# connectors.net
KiCad netlist of a schematic drawn in Altium Designer
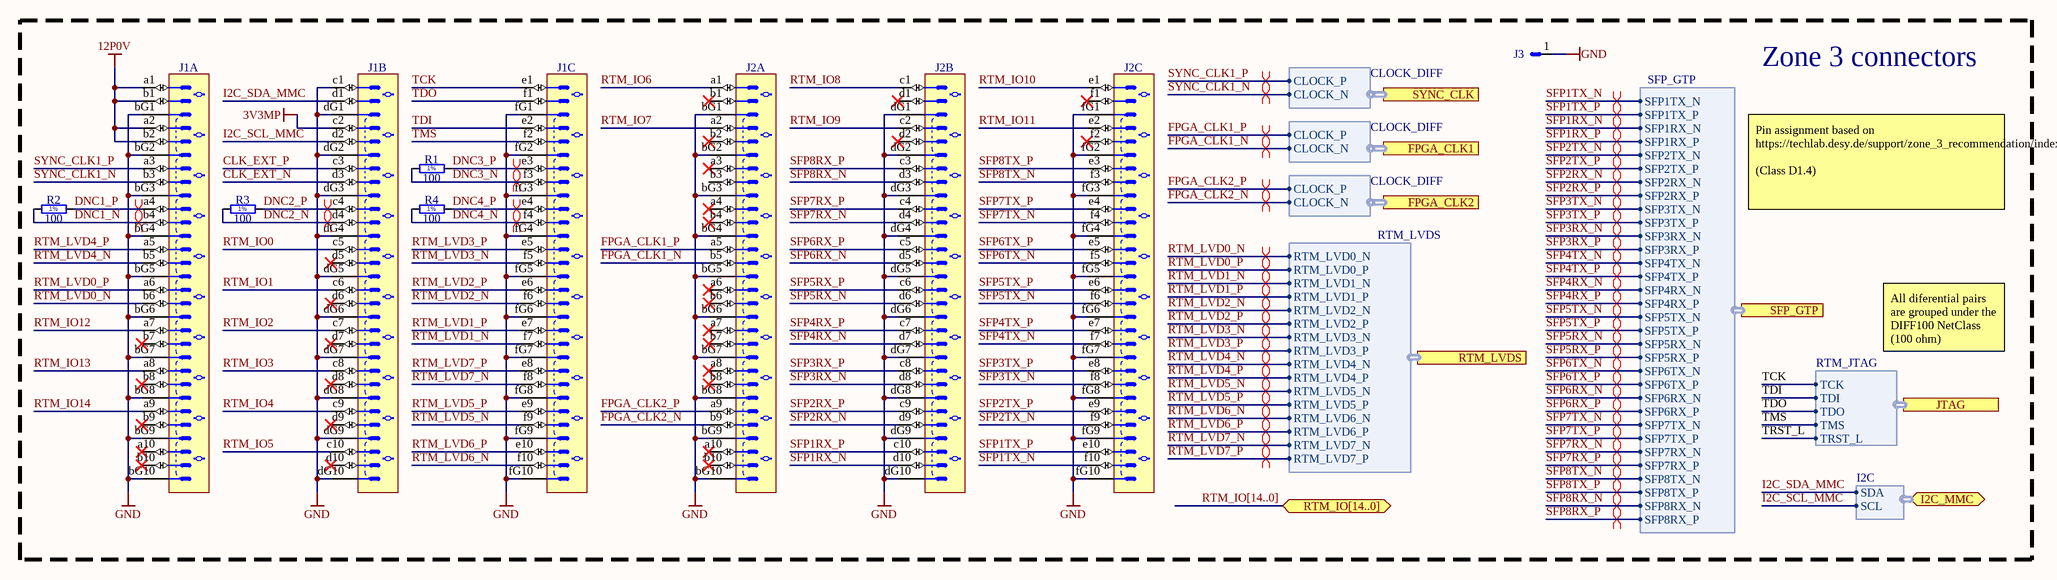
[diagram p0: connectors.SchDoc]

(export (version "E")
  (design (tool "Eeschema 10.0.6"))
  (components
    (comp (ref "J1")
      (value "Advanced TCA")
      (footprint "TYCO_6469183-1")
      (description "Connector 60 ATCA Male 30 Pairs (60 Signals) + 3x10 Ground")
      (fields
        (field (name "PART NUMBER") "TYCO_6469183-1")
        (field (name "MANUFACTURER") "TYCO ELECTRONICS")
        (field (name "AUTHOR") "CERN DEM JLC")
      )
      (libsource (lib "Connectors") (part "Connector ATCA 60+30 Male"))
    )
    (comp (ref "J2")
      (value "Advanced TCA")
      (footprint "TYCO_6469183-1")
      (description "Connector 60 ATCA Male 30 Pairs (60 Signals) + 3x10 Ground")
      (fields
        (field (name "PART NUMBER") "TYCO_6469183-1")
        (field (name "MANUFACTURER") "TYCO ELECTRONICS")
        (field (name "AUTHOR") "CERN DEM JLC")
      )
      (libsource (lib "Connectors") (part "Connector ATCA 60+30 Male"))
    )
    (comp (ref "J3")
      (value "~")
      (footprint "TYCO_1469265-1")
      (description "Single Pin Male")
      (fields
        (field (name "PART NUMBER") "TYCO_1469265-1")
        (field (name "MANUFACTURER") "TYCO ELECTRONICS")
        (field (name "AUTHOR") "CERN DEM JLC")
      )
      (libsource (lib "Connectors") (part "Single Pin Male"))
    )
    (comp (ref "R1")
      (value "100")
      (footprint "RESC1608X55N")
      (description "Resistor - 1%")
      (fields
        (field (name "PART NUMBER") "R0603_100R_1%_0.1W_100PPM")
        (field (name "POWER") "0.1W")
        (field (name "AUTHOR") "CERN DEM JLC")
      )
      (libsource (lib "Resistors") (part "Resistor - 1%"))
    )
    (comp (ref "R2")
      (value "100")
      (footprint "RESC1608X55N")
      (description "Resistor - 1%")
      (fields
        (field (name "PART NUMBER") "R0603_100R_1%_0.1W_100PPM")
        (field (name "POWER") "0.1W")
        (field (name "AUTHOR") "CERN DEM JLC")
      )
      (libsource (lib "Resistors") (part "Resistor - 1%"))
    )
    (comp (ref "R3")
      (value "100")
      (footprint "RESC1608X55N")
      (description "Resistor - 1%")
      (fields
        (field (name "PART NUMBER") "R0603_100R_1%_0.1W_100PPM")
        (field (name "POWER") "0.1W")
        (field (name "AUTHOR") "CERN DEM JLC")
      )
      (libsource (lib "Resistors") (part "Resistor - 1%"))
    )
    (comp (ref "R4")
      (value "100")
      (footprint "RESC1608X55N")
      (description "Resistor - 1%")
      (fields
        (field (name "PART NUMBER") "R0603_100R_1%_0.1W_100PPM")
        (field (name "POWER") "0.1W")
        (field (name "AUTHOR") "CERN DEM JLC")
      )
      (libsource (lib "Resistors") (part "Resistor - 1%"))
    )
  )
  (nets
    (net (code "6") (name "/CLK_EXT_N") (class "Default")
      (node (ref "J1") (pin "d3") (pinfunction "d3_d3") (pintype "bidirectional"))
    )
    (net (code "7") (name "/CLK_EXT_P") (class "Default")
      (node (ref "J1") (pin "c3") (pinfunction "c3_c3") (pintype "bidirectional"))
    )
    (net (code "8") (name "/DNC1_N") (class "Default")
      (node (ref "J1") (pin "b4") (pinfunction "b4_b4") (pintype "bidirectional"))
      (node (ref "R2") (pin "1") (pinfunction "1_1") (pintype "passive"))
    )
    (net (code "9") (name "/DNC1_P") (class "Default")
      (node (ref "J1") (pin "a4") (pinfunction "a4_a4") (pintype "bidirectional"))
      (node (ref "R2") (pin "2") (pinfunction "2_2") (pintype "passive"))
    )
    (net (code "10") (name "/DNC2_N") (class "Default")
      (node (ref "J1") (pin "d4") (pinfunction "d4_d4") (pintype "bidirectional"))
      (node (ref "R3") (pin "1") (pinfunction "1_1") (pintype "passive"))
    )
    (net (code "11") (name "/DNC2_P") (class "Default")
      (node (ref "J1") (pin "c4") (pinfunction "c4_c4") (pintype "bidirectional"))
      (node (ref "R3") (pin "2") (pinfunction "2_2") (pintype "passive"))
    )
    (net (code "12") (name "/DNC3_N") (class "Default")
      (node (ref "J1") (pin "f3") (pinfunction "f3_f3") (pintype "bidirectional"))
      (node (ref "R1") (pin "1") (pinfunction "1_1") (pintype "passive"))
    )
    (net (code "13") (name "/DNC3_P") (class "Default")
      (node (ref "J1") (pin "e3") (pinfunction "e3_e3") (pintype "bidirectional"))
      (node (ref "R1") (pin "2") (pinfunction "2_2") (pintype "passive"))
    )
    (net (code "14") (name "/DNC4_N") (class "Default")
      (node (ref "J1") (pin "f4") (pinfunction "f4_f4") (pintype "bidirectional"))
      (node (ref "R4") (pin "1") (pinfunction "1_1") (pintype "passive"))
    )
    (net (code "15") (name "/DNC4_P") (class "Default")
      (node (ref "J1") (pin "e4") (pinfunction "e4_e4") (pintype "bidirectional"))
      (node (ref "R4") (pin "2") (pinfunction "2_2") (pintype "passive"))
    )
    (net (code "16") (name "/FPGA_CLK1_N") (class "Default")
      (node (ref "J2") (pin "b5") (pinfunction "b5_b5") (pintype "bidirectional"))
    )
    (net (code "17") (name "/FPGA_CLK1_P") (class "Default")
      (node (ref "J2") (pin "a5") (pinfunction "a5_a5") (pintype "bidirectional"))
    )
    (net (code "18") (name "/FPGA_CLK2_N") (class "Default")
      (node (ref "J2") (pin "b9") (pinfunction "b9_b9") (pintype "bidirectional"))
    )
    (net (code "19") (name "/FPGA_CLK2_P") (class "Default")
      (node (ref "J2") (pin "a9") (pinfunction "a9_a9") (pintype "bidirectional"))
    )
    (net (code "20") (name "/I2C_SCL_MMC") (class "Default")
      (node (ref "J1") (pin "d2") (pinfunction "d2_d2") (pintype "bidirectional"))
    )
    (net (code "21") (name "/I2C_SDA_MMC") (class "Default")
      (node (ref "J1") (pin "d1") (pinfunction "d1_d1") (pintype "bidirectional"))
    )
    (net (code "22") (name "/RTM_IO0") (class "Default")
      (node (ref "J1") (pin "c5") (pinfunction "c5_c5") (pintype "bidirectional"))
    )
    (net (code "23") (name "/RTM_IO1") (class "Default")
      (node (ref "J1") (pin "c6") (pinfunction "c6_c6") (pintype "bidirectional"))
    )
    (net (code "24") (name "/RTM_IO2") (class "Default")
      (node (ref "J1") (pin "c7") (pinfunction "c7_c7") (pintype "bidirectional"))
    )
    (net (code "25") (name "/RTM_IO3") (class "Default")
      (node (ref "J1") (pin "c8") (pinfunction "c8_c8") (pintype "bidirectional"))
    )
    (net (code "26") (name "/RTM_IO4") (class "Default")
      (node (ref "J1") (pin "c9") (pinfunction "c9_c9") (pintype "bidirectional"))
    )
    (net (code "27") (name "/RTM_IO5") (class "Default")
      (node (ref "J1") (pin "c10") (pinfunction "c10_c10") (pintype "bidirectional"))
    )
    (net (code "28") (name "/RTM_IO6") (class "Default")
      (node (ref "J2") (pin "a1") (pinfunction "a1_a1") (pintype "bidirectional"))
    )
    (net (code "29") (name "/RTM_IO7") (class "Default")
      (node (ref "J2") (pin "a2") (pinfunction "a2_a2") (pintype "bidirectional"))
    )
    (net (code "30") (name "/RTM_IO8") (class "Default")
      (node (ref "J2") (pin "c1") (pinfunction "c1_c1") (pintype "bidirectional"))
    )
    (net (code "31") (name "/RTM_IO9") (class "Default")
      (node (ref "J2") (pin "c2") (pinfunction "c2_c2") (pintype "bidirectional"))
    )
    (net (code "32") (name "/RTM_IO10") (class "Default")
      (node (ref "J2") (pin "e1") (pinfunction "e1_e1") (pintype "bidirectional"))
    )
    (net (code "33") (name "/RTM_IO11") (class "Default")
      (node (ref "J2") (pin "e2") (pinfunction "e2_e2") (pintype "bidirectional"))
    )
    (net (code "34") (name "/RTM_IO12") (class "Default")
      (node (ref "J1") (pin "a7") (pinfunction "a7_a7") (pintype "bidirectional"))
    )
    (net (code "35") (name "/RTM_IO13") (class "Default")
      (node (ref "J1") (pin "a8") (pinfunction "a8_a8") (pintype "bidirectional"))
    )
    (net (code "36") (name "/RTM_IO14") (class "Default")
      (node (ref "J1") (pin "a9") (pinfunction "a9_a9") (pintype "bidirectional"))
    )
    (net (code "38") (name "/RTM_LVD0_N") (class "Default")
      (node (ref "J1") (pin "b6") (pinfunction "b6_b6") (pintype "bidirectional"))
    )
    (net (code "39") (name "/RTM_LVD0_P") (class "Default")
      (node (ref "J1") (pin "a6") (pinfunction "a6_a6") (pintype "bidirectional"))
    )
    (net (code "40") (name "/RTM_LVD1_N") (class "Default")
      (node (ref "J1") (pin "f7") (pinfunction "f7_f7") (pintype "bidirectional"))
    )
    (net (code "41") (name "/RTM_LVD1_P") (class "Default")
      (node (ref "J1") (pin "e7") (pinfunction "e7_e7") (pintype "bidirectional"))
    )
    (net (code "42") (name "/RTM_LVD2_N") (class "Default")
      (node (ref "J1") (pin "f6") (pinfunction "f6_f6") (pintype "bidirectional"))
    )
    (net (code "43") (name "/RTM_LVD2_P") (class "Default")
      (node (ref "J1") (pin "e6") (pinfunction "e6_e6") (pintype "bidirectional"))
    )
    (net (code "44") (name "/RTM_LVD3_N") (class "Default")
      (node (ref "J1") (pin "f5") (pinfunction "f5_f5") (pintype "bidirectional"))
    )
    (net (code "45") (name "/RTM_LVD3_P") (class "Default")
      (node (ref "J1") (pin "e5") (pinfunction "e5_e5") (pintype "bidirectional"))
    )
    (net (code "46") (name "/RTM_LVD4_N") (class "Default")
      (node (ref "J1") (pin "b5") (pinfunction "b5_b5") (pintype "bidirectional"))
    )
    (net (code "47") (name "/RTM_LVD4_P") (class "Default")
      (node (ref "J1") (pin "a5") (pinfunction "a5_a5") (pintype "bidirectional"))
    )
    (net (code "48") (name "/RTM_LVD5_N") (class "Default")
      (node (ref "J1") (pin "f9") (pinfunction "f9_f9") (pintype "bidirectional"))
    )
    (net (code "49") (name "/RTM_LVD5_P") (class "Default")
      (node (ref "J1") (pin "e9") (pinfunction "e9_e9") (pintype "bidirectional"))
    )
    (net (code "50") (name "/RTM_LVD6_N") (class "Default")
      (node (ref "J1") (pin "f10") (pinfunction "f10_f10") (pintype "bidirectional"))
    )
    (net (code "51") (name "/RTM_LVD6_P") (class "Default")
      (node (ref "J1") (pin "e10") (pinfunction "e10_e10") (pintype "bidirectional"))
    )
    (net (code "52") (name "/RTM_LVD7_N") (class "Default")
      (node (ref "J1") (pin "f8") (pinfunction "f8_f8") (pintype "bidirectional"))
    )
    (net (code "53") (name "/RTM_LVD7_P") (class "Default")
      (node (ref "J1") (pin "e8") (pinfunction "e8_e8") (pintype "bidirectional"))
    )
    (net (code "54") (name "/SFP1RX_N") (class "Default")
      (node (ref "J2") (pin "d10") (pinfunction "d10_d10") (pintype "bidirectional"))
    )
    (net (code "55") (name "/SFP1RX_P") (class "Default")
      (node (ref "J2") (pin "c10") (pinfunction "c10_c10") (pintype "bidirectional"))
    )
    (net (code "56") (name "/SFP1TX_N") (class "Default")
      (node (ref "J2") (pin "f10") (pinfunction "f10_f10") (pintype "bidirectional"))
    )
    (net (code "57") (name "/SFP1TX_P") (class "Default")
      (node (ref "J2") (pin "e10") (pinfunction "e10_e10") (pintype "bidirectional"))
    )
    (net (code "58") (name "/SFP2RX_N") (class "Default")
      (node (ref "J2") (pin "d9") (pinfunction "d9_d9") (pintype "bidirectional"))
    )
    (net (code "59") (name "/SFP2RX_P") (class "Default")
      (node (ref "J2") (pin "c9") (pinfunction "c9_c9") (pintype "bidirectional"))
    )
    (net (code "60") (name "/SFP2TX_N") (class "Default")
      (node (ref "J2") (pin "f9") (pinfunction "f9_f9") (pintype "bidirectional"))
    )
    (net (code "61") (name "/SFP2TX_P") (class "Default")
      (node (ref "J2") (pin "e9") (pinfunction "e9_e9") (pintype "bidirectional"))
    )
    (net (code "62") (name "/SFP3RX_N") (class "Default")
      (node (ref "J2") (pin "d8") (pinfunction "d8_d8") (pintype "bidirectional"))
    )
    (net (code "63") (name "/SFP3RX_P") (class "Default")
      (node (ref "J2") (pin "c8") (pinfunction "c8_c8") (pintype "bidirectional"))
    )
    (net (code "64") (name "/SFP3TX_N") (class "Default")
      (node (ref "J2") (pin "f8") (pinfunction "f8_f8") (pintype "bidirectional"))
    )
    (net (code "65") (name "/SFP3TX_P") (class "Default")
      (node (ref "J2") (pin "e8") (pinfunction "e8_e8") (pintype "bidirectional"))
    )
    (net (code "66") (name "/SFP4RX_N") (class "Default")
      (node (ref "J2") (pin "d7") (pinfunction "d7_d7") (pintype "bidirectional"))
    )
    (net (code "67") (name "/SFP4RX_P") (class "Default")
      (node (ref "J2") (pin "c7") (pinfunction "c7_c7") (pintype "bidirectional"))
    )
    (net (code "68") (name "/SFP4TX_N") (class "Default")
      (node (ref "J2") (pin "f7") (pinfunction "f7_f7") (pintype "bidirectional"))
    )
    (net (code "69") (name "/SFP4TX_P") (class "Default")
      (node (ref "J2") (pin "e7") (pinfunction "e7_e7") (pintype "bidirectional"))
    )
    (net (code "70") (name "/SFP5RX_N") (class "Default")
      (node (ref "J2") (pin "d6") (pinfunction "d6_d6") (pintype "bidirectional"))
    )
    (net (code "71") (name "/SFP5RX_P") (class "Default")
      (node (ref "J2") (pin "c6") (pinfunction "c6_c6") (pintype "bidirectional"))
    )
    (net (code "72") (name "/SFP5TX_N") (class "Default")
      (node (ref "J2") (pin "f6") (pinfunction "f6_f6") (pintype "bidirectional"))
    )
    (net (code "73") (name "/SFP5TX_P") (class "Default")
      (node (ref "J2") (pin "e6") (pinfunction "e6_e6") (pintype "bidirectional"))
    )
    (net (code "74") (name "/SFP6RX_N") (class "Default")
      (node (ref "J2") (pin "d5") (pinfunction "d5_d5") (pintype "bidirectional"))
    )
    (net (code "75") (name "/SFP6RX_P") (class "Default")
      (node (ref "J2") (pin "c5") (pinfunction "c5_c5") (pintype "bidirectional"))
    )
    (net (code "76") (name "/SFP6TX_N") (class "Default")
      (node (ref "J2") (pin "f5") (pinfunction "f5_f5") (pintype "bidirectional"))
    )
    (net (code "77") (name "/SFP6TX_P") (class "Default")
      (node (ref "J2") (pin "e5") (pinfunction "e5_e5") (pintype "bidirectional"))
    )
    (net (code "78") (name "/SFP7RX_N") (class "Default")
      (node (ref "J2") (pin "d4") (pinfunction "d4_d4") (pintype "bidirectional"))
    )
    (net (code "79") (name "/SFP7RX_P") (class "Default")
      (node (ref "J2") (pin "c4") (pinfunction "c4_c4") (pintype "bidirectional"))
    )
    (net (code "80") (name "/SFP7TX_N") (class "Default")
      (node (ref "J2") (pin "f4") (pinfunction "f4_f4") (pintype "bidirectional"))
    )
    (net (code "81") (name "/SFP7TX_P") (class "Default")
      (node (ref "J2") (pin "e4") (pinfunction "e4_e4") (pintype "bidirectional"))
    )
    (net (code "82") (name "/SFP8RX_N") (class "Default")
      (node (ref "J2") (pin "d3") (pinfunction "d3_d3") (pintype "bidirectional"))
    )
    (net (code "83") (name "/SFP8RX_P") (class "Default")
      (node (ref "J2") (pin "c3") (pinfunction "c3_c3") (pintype "bidirectional"))
    )
    (net (code "84") (name "/SFP8TX_N") (class "Default")
      (node (ref "J2") (pin "f3") (pinfunction "f3_f3") (pintype "bidirectional"))
    )
    (net (code "85") (name "/SFP8TX_P") (class "Default")
      (node (ref "J2") (pin "e3") (pinfunction "e3_e3") (pintype "bidirectional"))
    )
    (net (code "86") (name "/SYNC_CLK1_N") (class "Default")
      (node (ref "J1") (pin "b3") (pinfunction "b3_b3") (pintype "bidirectional"))
    )
    (net (code "87") (name "/SYNC_CLK1_P") (class "Default")
      (node (ref "J1") (pin "a3") (pinfunction "a3_a3") (pintype "bidirectional"))
    )
    (net (code "88") (name "/TCK") (class "Default")
      (node (ref "J1") (pin "e1") (pinfunction "e1_e1") (pintype "bidirectional"))
    )
    (net (code "89") (name "/TDI") (class "Default")
      (node (ref "J1") (pin "e2") (pinfunction "e2_e2") (pintype "bidirectional"))
    )
    (net (code "90") (name "/TDO") (class "Default")
      (node (ref "J1") (pin "f1") (pinfunction "f1_f1") (pintype "bidirectional"))
    )
    (net (code "91") (name "/TMS") (class "Default")
      (node (ref "J1") (pin "f2") (pinfunction "f2_f2") (pintype "bidirectional"))
    )
    (net (code "98") (name "3V3MP") (class "Default")
      (node (ref "J1") (pin "c2") (pinfunction "c2_c2") (pintype "bidirectional"))
    )
    (net (code "99") (name "12P0V") (class "Default")
      (node (ref "J1") (pin "a1") (pinfunction "a1_a1") (pintype "bidirectional"))
      (node (ref "J1") (pin "a2") (pinfunction "a2_a2") (pintype "bidirectional"))
      (node (ref "J1") (pin "b1") (pinfunction "b1_b1") (pintype "bidirectional"))
      (node (ref "J1") (pin "b2") (pinfunction "b2_b2") (pintype "bidirectional"))
    )
    (net (code "100") (name "GND") (class "Default")
      (node (ref "J1") (pin "bG1") (pinfunction "bG1_bG1") (pintype "power_in"))
      (node (ref "J1") (pin "bG10") (pinfunction "bG10_bG10") (pintype "power_in"))
      (node (ref "J1") (pin "bG2") (pinfunction "bG2_bG2") (pintype "power_in"))
      (node (ref "J1") (pin "bG3") (pinfunction "bG3_bG3") (pintype "power_in"))
      (node (ref "J1") (pin "bG4") (pinfunction "bG4_bG4") (pintype "power_in"))
      (node (ref "J1") (pin "bG5") (pinfunction "bG5_bG5") (pintype "power_in"))
      (node (ref "J1") (pin "bG6") (pinfunction "bG6_bG6") (pintype "power_in"))
      (node (ref "J1") (pin "bG7") (pinfunction "bG7_bG7") (pintype "power_in"))
      (node (ref "J1") (pin "bG8") (pinfunction "bG8_bG8") (pintype "power_in"))
      (node (ref "J1") (pin "bG9") (pinfunction "bG9_bG9") (pintype "power_in"))
      (node (ref "J1") (pin "c1") (pinfunction "c1_c1") (pintype "bidirectional"))
      (node (ref "J1") (pin "dG1") (pinfunction "dG1_dG1") (pintype "power_in"))
      (node (ref "J1") (pin "dG10") (pinfunction "dG10_dG10") (pintype "power_in"))
      (node (ref "J1") (pin "dG2") (pinfunction "dG2_dG2") (pintype "power_in"))
      (node (ref "J1") (pin "dG3") (pinfunction "dG3_dG3") (pintype "power_in"))
      (node (ref "J1") (pin "dG4") (pinfunction "dG4_dG4") (pintype "power_in"))
      (node (ref "J1") (pin "dG5") (pinfunction "dG5_dG5") (pintype "power_in"))
      (node (ref "J1") (pin "dG6") (pinfunction "dG6_dG6") (pintype "power_in"))
      (node (ref "J1") (pin "dG7") (pinfunction "dG7_dG7") (pintype "power_in"))
      (node (ref "J1") (pin "dG8") (pinfunction "dG8_dG8") (pintype "power_in"))
      (node (ref "J1") (pin "dG9") (pinfunction "dG9_dG9") (pintype "power_in"))
      (node (ref "J1") (pin "fG1") (pinfunction "fG1_fG1") (pintype "power_in"))
      (node (ref "J1") (pin "fG10") (pinfunction "fG10_fG10") (pintype "power_in"))
      (node (ref "J1") (pin "fG2") (pinfunction "fG2_fG2") (pintype "power_in"))
      (node (ref "J1") (pin "fG3") (pinfunction "fG3_fG3") (pintype "power_in"))
      (node (ref "J1") (pin "fG4") (pinfunction "fG4_fG4") (pintype "power_in"))
      (node (ref "J1") (pin "fG5") (pinfunction "fG5_fG5") (pintype "power_in"))
      (node (ref "J1") (pin "fG6") (pinfunction "fG6_fG6") (pintype "power_in"))
      (node (ref "J1") (pin "fG7") (pinfunction "fG7_fG7") (pintype "power_in"))
      (node (ref "J1") (pin "fG8") (pinfunction "fG8_fG8") (pintype "power_in"))
      (node (ref "J1") (pin "fG9") (pinfunction "fG9_fG9") (pintype "power_in"))
      (node (ref "J2") (pin "bG1") (pinfunction "bG1_bG1") (pintype "power_in"))
      (node (ref "J2") (pin "bG10") (pinfunction "bG10_bG10") (pintype "power_in"))
      (node (ref "J2") (pin "bG2") (pinfunction "bG2_bG2") (pintype "power_in"))
      (node (ref "J2") (pin "bG3") (pinfunction "bG3_bG3") (pintype "power_in"))
      (node (ref "J2") (pin "bG4") (pinfunction "bG4_bG4") (pintype "power_in"))
      (node (ref "J2") (pin "bG5") (pinfunction "bG5_bG5") (pintype "power_in"))
      (node (ref "J2") (pin "bG6") (pinfunction "bG6_bG6") (pintype "power_in"))
      (node (ref "J2") (pin "bG7") (pinfunction "bG7_bG7") (pintype "power_in"))
      (node (ref "J2") (pin "bG8") (pinfunction "bG8_bG8") (pintype "power_in"))
      (node (ref "J2") (pin "bG9") (pinfunction "bG9_bG9") (pintype "power_in"))
      (node (ref "J2") (pin "dG1") (pinfunction "dG1_dG1") (pintype "power_in"))
      (node (ref "J2") (pin "dG10") (pinfunction "dG10_dG10") (pintype "power_in"))
      (node (ref "J2") (pin "dG2") (pinfunction "dG2_dG2") (pintype "power_in"))
      (node (ref "J2") (pin "dG3") (pinfunction "dG3_dG3") (pintype "power_in"))
      (node (ref "J2") (pin "dG4") (pinfunction "dG4_dG4") (pintype "power_in"))
      (node (ref "J2") (pin "dG5") (pinfunction "dG5_dG5") (pintype "power_in"))
      (node (ref "J2") (pin "dG6") (pinfunction "dG6_dG6") (pintype "power_in"))
      (node (ref "J2") (pin "dG7") (pinfunction "dG7_dG7") (pintype "power_in"))
      (node (ref "J2") (pin "dG8") (pinfunction "dG8_dG8") (pintype "power_in"))
      (node (ref "J2") (pin "dG9") (pinfunction "dG9_dG9") (pintype "power_in"))
      (node (ref "J2") (pin "fG1") (pinfunction "fG1_fG1") (pintype "power_in"))
      (node (ref "J2") (pin "fG10") (pinfunction "fG10_fG10") (pintype "power_in"))
      (node (ref "J2") (pin "fG2") (pinfunction "fG2_fG2") (pintype "power_in"))
      (node (ref "J2") (pin "fG3") (pinfunction "fG3_fG3") (pintype "power_in"))
      (node (ref "J2") (pin "fG4") (pinfunction "fG4_fG4") (pintype "power_in"))
      (node (ref "J2") (pin "fG5") (pinfunction "fG5_fG5") (pintype "power_in"))
      (node (ref "J2") (pin "fG6") (pinfunction "fG6_fG6") (pintype "power_in"))
      (node (ref "J2") (pin "fG7") (pinfunction "fG7_fG7") (pintype "power_in"))
      (node (ref "J2") (pin "fG8") (pinfunction "fG8_fG8") (pintype "power_in"))
      (node (ref "J2") (pin "fG9") (pinfunction "fG9_fG9") (pintype "power_in"))
      (node (ref "J3") (pin "1") (pinfunction "1_1") (pintype "bidirectional"))
    )
    (net (code "101") (name "unconnected-(J1-Pada10)") (class "Default")
      (node (ref "J1") (pin "a10") (pinfunction "a10_a10") (pintype "bidirectional+no_connect"))
    )
    (net (code "102") (name "unconnected-(J1-Padb7)") (class "Default")
      (node (ref "J1") (pin "b7") (pinfunction "b7_b7") (pintype "bidirectional+no_connect"))
    )
    (net (code "103") (name "unconnected-(J1-Padb8)") (class "Default")
      (node (ref "J1") (pin "b8") (pinfunction "b8_b8") (pintype "bidirectional+no_connect"))
    )
    (net (code "104") (name "unconnected-(J1-Padb9)") (class "Default")
      (node (ref "J1") (pin "b9") (pinfunction "b9_b9") (pintype "bidirectional+no_connect"))
    )
    (net (code "105") (name "unconnected-(J1-Padb10)") (class "Default")
      (node (ref "J1") (pin "b10") (pinfunction "b10_b10") (pintype "bidirectional+no_connect"))
    )
    (net (code "106") (name "unconnected-(J1-Padd5)") (class "Default")
      (node (ref "J1") (pin "d5") (pinfunction "d5_d5") (pintype "bidirectional+no_connect"))
    )
    (net (code "107") (name "unconnected-(J1-Padd6)") (class "Default")
      (node (ref "J1") (pin "d6") (pinfunction "d6_d6") (pintype "bidirectional+no_connect"))
    )
    (net (code "108") (name "unconnected-(J1-Padd7)") (class "Default")
      (node (ref "J1") (pin "d7") (pinfunction "d7_d7") (pintype "bidirectional+no_connect"))
    )
    (net (code "109") (name "unconnected-(J1-Padd8)") (class "Default")
      (node (ref "J1") (pin "d8") (pinfunction "d8_d8") (pintype "bidirectional+no_connect"))
    )
    (net (code "110") (name "unconnected-(J1-Padd9)") (class "Default")
      (node (ref "J1") (pin "d9") (pinfunction "d9_d9") (pintype "bidirectional+no_connect"))
    )
    (net (code "111") (name "unconnected-(J1-Padd10)") (class "Default")
      (node (ref "J1") (pin "d10") (pinfunction "d10_d10") (pintype "bidirectional+no_connect"))
    )
    (net (code "112") (name "unconnected-(J2-Pada3)") (class "Default")
      (node (ref "J2") (pin "a3") (pinfunction "a3_a3") (pintype "bidirectional+no_connect"))
    )
    (net (code "113") (name "unconnected-(J2-Pada4)") (class "Default")
      (node (ref "J2") (pin "a4") (pinfunction "a4_a4") (pintype "bidirectional+no_connect"))
    )
    (net (code "114") (name "unconnected-(J2-Pada6)") (class "Default")
      (node (ref "J2") (pin "a6") (pinfunction "a6_a6") (pintype "bidirectional+no_connect"))
    )
    (net (code "115") (name "unconnected-(J2-Pada7)") (class "Default")
      (node (ref "J2") (pin "a7") (pinfunction "a7_a7") (pintype "bidirectional+no_connect"))
    )
    (net (code "116") (name "unconnected-(J2-Pada8)") (class "Default")
      (node (ref "J2") (pin "a8") (pinfunction "a8_a8") (pintype "bidirectional+no_connect"))
    )
    (net (code "117") (name "unconnected-(J2-Pada10)") (class "Default")
      (node (ref "J2") (pin "a10") (pinfunction "a10_a10") (pintype "bidirectional+no_connect"))
    )
    (net (code "118") (name "unconnected-(J2-Padb1)") (class "Default")
      (node (ref "J2") (pin "b1") (pinfunction "b1_b1") (pintype "bidirectional+no_connect"))
    )
    (net (code "119") (name "unconnected-(J2-Padb2)") (class "Default")
      (node (ref "J2") (pin "b2") (pinfunction "b2_b2") (pintype "bidirectional+no_connect"))
    )
    (net (code "120") (name "unconnected-(J2-Padb3)") (class "Default")
      (node (ref "J2") (pin "b3") (pinfunction "b3_b3") (pintype "bidirectional"))
    )
    (net (code "121") (name "unconnected-(J2-Padb4)") (class "Default")
      (node (ref "J2") (pin "b4") (pinfunction "b4_b4") (pintype "bidirectional+no_connect"))
    )
    (net (code "122") (name "unconnected-(J2-Padb6)") (class "Default")
      (node (ref "J2") (pin "b6") (pinfunction "b6_b6") (pintype "bidirectional+no_connect"))
    )
    (net (code "123") (name "unconnected-(J2-Padb7)") (class "Default")
      (node (ref "J2") (pin "b7") (pinfunction "b7_b7") (pintype "bidirectional+no_connect"))
    )
    (net (code "124") (name "unconnected-(J2-Padb8)") (class "Default")
      (node (ref "J2") (pin "b8") (pinfunction "b8_b8") (pintype "bidirectional+no_connect"))
    )
    (net (code "125") (name "unconnected-(J2-Padb10)") (class "Default")
      (node (ref "J2") (pin "b10") (pinfunction "b10_b10") (pintype "bidirectional+no_connect"))
    )
    (net (code "126") (name "unconnected-(J2-Padd1)") (class "Default")
      (node (ref "J2") (pin "d1") (pinfunction "d1_d1") (pintype "bidirectional+no_connect"))
    )
    (net (code "127") (name "unconnected-(J2-Padd2)") (class "Default")
      (node (ref "J2") (pin "d2") (pinfunction "d2_d2") (pintype "bidirectional+no_connect"))
    )
    (net (code "128") (name "unconnected-(J2-Padf1)") (class "Default")
      (node (ref "J2") (pin "f1") (pinfunction "f1_f1") (pintype "bidirectional+no_connect"))
    )
    (net (code "129") (name "unconnected-(J2-Padf2)") (class "Default")
      (node (ref "J2") (pin "f2") (pinfunction "f2_f2") (pintype "bidirectional+no_connect"))
    )
  )
)
